# RJ45_Power_Reg.net
KiCad netlist of a schematic drawn in Altium Designer
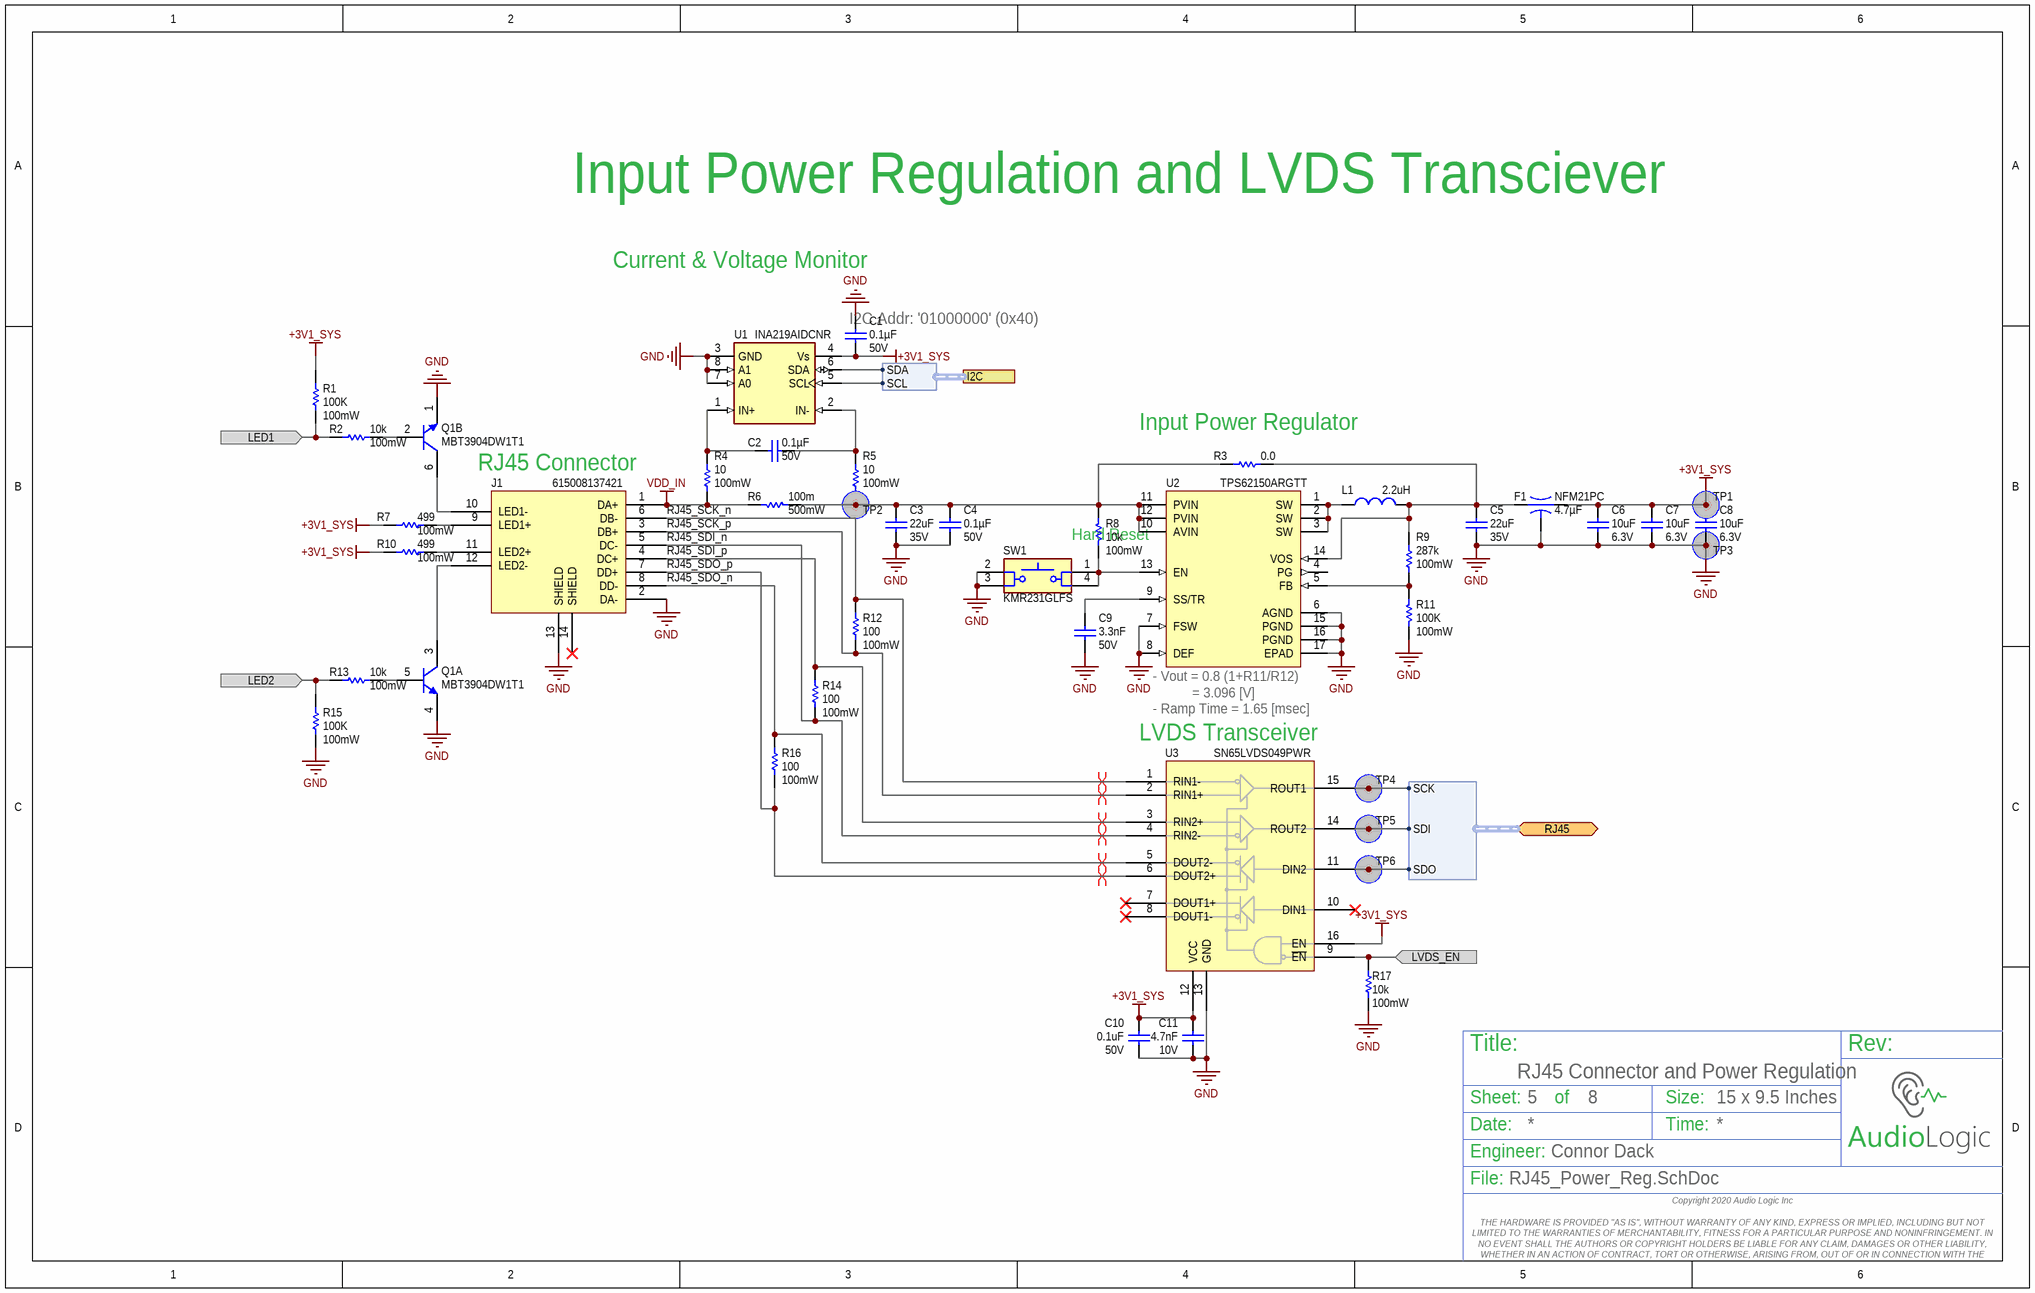
[diagram p0: RJ45_Power_Reg.SchDoc]

(export (version "E")
  (design (tool "Eeschema 10.0.6"))
  (components
    (comp (ref "C1")
      (value "C1005X7R1H104K050BE")
      (footprint "2-0402_L")
      (description "CAP CER 0.1UF 50V X7R 0402")
      (fields
        (field (name "MANUFACTURER") "TDK Corporation")
        (field (name "TOLERANCE") "±10%")
        (field (name "VOLTAGE - RATED") "50V")
        (field (name "CAPACITANCE") "0.1µF")
      )
      (libsource (lib "Schematic_Components") (part "C1005X7R1H104K050BE"))
    )
    (comp (ref "C2")
      (value "C1005X7R1H104K050BE")
      (footprint "2-0402_L")
      (description "CAP CER 0.1UF 50V X7R 0402")
      (fields
        (field (name "MANUFACTURER") "TDK Corporation")
        (field (name "TOLERANCE") "±10%")
        (field (name "VOLTAGE - RATED") "50V")
        (field (name "CAPACITANCE") "0.1µF")
      )
      (libsource (lib "Schematic_Components") (part "C1005X7R1H104K050BE"))
    )
    (comp (ref "C3")
      (value "C3216X5R1V226M160AC")
      (footprint "C1206")
      (description "CAP CER 22UF 35V X5R 1206")
      (fields
        (field (name "MANUFACTURER") "TDK")
        (field (name "TOLERANCE") "20%")
        (field (name "VOLTAGE RATING") "35V")
        (field (name "CAPACITANCE") "22uF")
      )
      (libsource (lib "Schematic_Components") (part "C3216X5R1V226M160AC"))
    )
    (comp (ref "C4")
      (value "C1005X7R1H104K050BE")
      (footprint "2-0402_L")
      (description "CAP CER 0.1UF 50V X7R 0402")
      (fields
        (field (name "MANUFACTURER") "TDK Corporation")
        (field (name "TOLERANCE") "±10%")
        (field (name "VOLTAGE - RATED") "50V")
        (field (name "CAPACITANCE") "0.1µF")
      )
      (libsource (lib "Schematic_Components") (part "C1005X7R1H104K050BE"))
    )
    (comp (ref "C5")
      (value "C3216X5R1V226M160AC")
      (footprint "C1206")
      (description "CAP CER 22UF 35V X5R 1206")
      (fields
        (field (name "MANUFACTURER") "TDK")
        (field (name "TOLERANCE") "20%")
        (field (name "VOLTAGE") "35V")
        (field (name "CAPACITANCE") "22uF")
      )
      (libsource (lib "Schematic_Components") (part "C3216X5R1V226M160AC"))
    )
    (comp (ref "C6")
      (value "JMK107ABJ106MAHT")
      (footprint "3-0603_L")
      (description "CAP CER 10UF 6.3V X5R 0603")
      (fields
        (field (name "MANUFACTURER") "Taiyo Yuden")
        (field (name "TOLERANCE") "20%")
        (field (name "VOLTAGE RATING (DC)") "6.3V")
        (field (name "CAPACITANCE") "10uF")
      )
      (libsource (lib "Schematic_Components") (part "JMK107ABJ106MAHT"))
    )
    (comp (ref "C7")
      (value "JMK107ABJ106MAHT")
      (footprint "3-0603_L")
      (description "CAP CER 10UF 6.3V X5R 0603")
      (fields
        (field (name "MANUFACTURER") "Taiyo Yuden")
        (field (name "TOLERANCE") "20%")
        (field (name "VOLTAGE RATING (DC)") "6.3V")
        (field (name "CAPACITANCE") "10uF")
      )
      (libsource (lib "Schematic_Components") (part "JMK107ABJ106MAHT"))
    )
    (comp (ref "C8")
      (value "JMK107ABJ106MAHT")
      (footprint "3-0603_L")
      (description "CAP CER 10UF 6.3V X5R 0603")
      (fields
        (field (name "MANUFACTURER") "Taiyo Yuden")
        (field (name "TOLERANCE") "20%")
        (field (name "VOLTAGE RATING (DC)") "6.3V")
        (field (name "CAPACITANCE") "10uF")
      )
      (libsource (lib "Schematic_Components") (part "JMK107ABJ106MAHT"))
    )
    (comp (ref "C9")
      (value "04025C332KAT2A")
      (footprint "CAPC1005X56X25NL10T15")
      (description "CAP CER 3300PF 50V X7R 0402")
      (fields
        (field (name "CAPACITANCE") "3.3nF")
        (field (name "MANUFACTURER") "AVX Interconnect / Elco")
        (field (name "TOLERANCE") "10%")
        (field (name "VOLTAGE RATING") "50V")
      )
      (libsource (lib "Altium Content Vault") (part "CAP"))
    )
    (comp (ref "C10")
      (value "UMK105B7104KVHF")
      (footprint "2-0402_L")
      (description "CAP CER 0.1uF 50V X7R +/-10% 0402 AEC-Q200")
      (fields
        (field (name "MANUFACTURER") "Taiyo Yuden")
        (field (name "TOLERANCE") "10%")
        (field (name "CAPACITANCE") "0.1uF")
        (field (name "VOLTAGE RATING") "50V")
      )
      (libsource (lib "Schematic_Components") (part "UMK105B7104KVHF"))
    )
    (comp (ref "C11")
      (value "C0603C472K8RACTU")
      (footprint "3-0603_L")
      (description "CAP CER 4700PF 10V X7R 0603")
      (fields
        (field (name "MANUFACTURER") "KEMET")
        (field (name "TOLERANCE") "10%")
        (field (name "VOLTAGE RATING (DC)") "10V")
        (field (name "CAPACITANCE") "4.7nF")
      )
      (libsource (lib "Schematic_Components_CD") (part "C0603C472K8RACTU"))
    )
    (comp (ref "F1")
      (value "NFM21PC")
      (footprint "NFM21PC")
      (description "CAP FEEDTHRU 4.7UF 20% 10V 0805")
      (fields
        (field (name "MANUFACTURER") "Murata Electronics North America")
        (field (name "TOLERANCE") "±20%")
        (field (name "CAPACITANCE") "4.7µF")
      )
      (libsource (lib "Schematic_Components") (part "NFM21PC475B1A3D"))
    )
    (comp (ref "J1")
      (value "CONN MOD JACK 8P8C R/A SHIELDED")
      (footprint "RJ45")
      (description "Jack Modular Connector 8p8c (RJ45, Ethernet) 90° Angle (Right) Shielded, EMI Finger Cat5")
      (fields
        (field (name "MANUFACTURER") "Wurth Electronics")
        (field (name "MANUFACTURER PART NUMBER") "615008137421")
      )
      (libsource (lib "Schematic_Components_CD") (part "615008137421"))
    )
    (comp (ref "L1")
      (value "2.2uH Ind")
      (footprint "XFL4020")
      (description "Fixed Inductors XFL4020 AEC-Q200 2.2 uH 20 % 8 A")
      (fields
        (field (name "MANUFACTURER") "Coilcraft")
        (field (name "MANUFACTURER PART NUMBER") "XFL4020-222MEB")
        (field (name "INDUCTANCE") "2.2uH")
      )
      (libsource (lib "Schematic_Components_CD") (part "XFL4020-222MEB"))
    )
    (comp (ref "Q1")
      (value "MBT3904DW1T1")
      (footprint "ADI-KS-6_SC70_L")
      (description "TRANS DUAL GP 200MA 40V SC88")
      (fields
        (field (name "MANUFACTURER") "ON Semiconductor")
        (field (name "MANUFACTURER PART NUMBER") "MBT3904DW1T1G")
        (field (name "SYMNAME") "MBT3904DW1T1")
      )
      (libsource (lib "Schematic_Components") (part "MBT3904DW1T1"))
    )
    (comp (ref "R1")
      (value "ERJ-2RKF1003X")
      (footprint "2-0402_R_L")
      (description "RES 100K OHM 1/10W 1% 0402 SMD")
      (fields
        (field (name "MANUFACTURER") "Panasonic - ECG")
        (field (name "POWER (WATTS)") "100mW")
        (field (name "TOLERANCE") "±1%")
        (field (name "RESISTANCE (OHMS)") "100K")
      )
      (libsource (lib "Schematic_Components") (part "ERJ-2RKF1003X"))
    )
    (comp (ref "R2")
      (value "ERJ-2RKF1002X")
      (footprint "2-0402_R_L")
      (description "RES 10K OHM 1/10W 1% 0402 SMD")
      (fields
        (field (name "MANUFACTURER") "Panasonic Electronic Components")
        (field (name "TOLERANCE") "±1%")
        (field (name "POWER (WATTS)") "100mW")
        (field (name "RESISTANCE (OHMS)") "10k")
      )
      (libsource (lib "Schematic_Components") (part "ERJ-2RKF1002X"))
    )
    (comp (ref "R3")
      (value "ERJ-6GEY0R00V")
      (footprint "6-0805_R_L")
      (description "RES 0.0 OHM 1/8W 0805 SMD")
      (fields
        (field (name "MANUFACTURER") "Panasonic - ECG")
        (field (name "TOLERANCE") "Jumper")
        (field (name "RESISTANCE (OHMS)") "0.0")
      )
      (libsource (lib "Schematic_Components") (part "ERJ-6GEY0R00V"))
    )
    (comp (ref "R4")
      (value "ERJ-2RKF10R0X")
      (footprint "2-0402_R_L")
      (description "RES 10 OHM 1/10W 1% 0402 SMD")
      (fields
        (field (name "MANUFACTURER") "Panasonic Electronic Components")
        (field (name "TOLERANCE") "±1%")
        (field (name "POWER (WATTS)") "100mW")
        (field (name "RESISTANCE (OHMS)") "10")
      )
      (libsource (lib "Schematic_Components") (part "ERJ-2RKF10R0X"))
    )
    (comp (ref "R5")
      (value "ERJ-2RKF10R0X")
      (footprint "2-0402_R_L")
      (description "RES 10 OHM 1/10W 1% 0402 SMD")
      (fields
        (field (name "MANUFACTURER") "Panasonic Electronic Components")
        (field (name "TOLERANCE") "±1%")
        (field (name "POWER (WATTS)") "100mW")
        (field (name "RESISTANCE (OHMS)") "10")
      )
      (libsource (lib "Schematic_Components") (part "ERJ-2RKF10R0X"))
    )
    (comp (ref "R6")
      (value "ERJ-6DSFR10V")
      (footprint "6-0805_R_L")
      (description "RES SMD 0.1 OHM 1% 1/2W 0805")
      (fields
        (field (name "MANUFACTURER") "Panasonic")
        (field (name "TOLERANCE") "1%")
        (field (name "MAX POWER DISSIPATION") "500mW")
        (field (name "RESISTANCE") "100m")
      )
      (libsource (lib "Schematic_Components") (part "ERJ-6DSFR10V"))
    )
    (comp (ref "R7")
      (value "ERJ-2RKF4990X")
      (footprint "2-0402_R_L")
      (description "RES 499 OHM 1/10W 1% 0402 SMD")
      (fields
        (field (name "MANUFACTURER") "Panasonic Electronic Components")
        (field (name "TOLERANCE") "±1%")
        (field (name "POWER (WATTS)") "100mW")
        (field (name "RESISTANCE (OHMS)") "499")
      )
      (libsource (lib "Schematic_Components") (part "ERJ-2RKF4990X"))
    )
    (comp (ref "R8")
      (value "ERJ-2RKF1002X")
      (footprint "2-0402_R_L")
      (description "RES 10K OHM 1/10W 1% 0402 SMD")
      (fields
        (field (name "MANUFACTURER") "Panasonic Electronic Components")
        (field (name "TOLERANCE") "±1%")
        (field (name "POWER (WATTS)") "100mW")
        (field (name "RESISTANCE (OHMS)") "10k")
      )
      (libsource (lib "Schematic_Components") (part "ERJ-2RKF1002X"))
    )
    (comp (ref "R9")
      (value "ERJ-2RKF2873X")
      (footprint "RESC1005X40X25NL05T05")
      (description "RES SMD 287K OHM 1% 1/10W 0402")
      (fields
        (field (name "MANUFACTURER") "Panasonic")
        (field (name "RESISTANCE") "287k")
        (field (name "POWER RATING") "100mW")
        (field (name "TOLERANCE") "1%")
      )
      (libsource (lib "Altium Content Vault") (part "RES"))
    )
    (comp (ref "R10")
      (value "ERJ-2RKF4990X")
      (footprint "2-0402_R_L")
      (description "RES 499 OHM 1/10W 1% 0402 SMD")
      (fields
        (field (name "MANUFACTURER") "Panasonic Electronic Components")
        (field (name "TOLERANCE") "±1%")
        (field (name "POWER (WATTS)") "100mW")
        (field (name "RESISTANCE (OHMS)") "499")
      )
      (libsource (lib "Schematic_Components") (part "ERJ-2RKF4990X"))
    )
    (comp (ref "R11")
      (value "ERJ-2RKF1003X")
      (footprint "2-0402_R_L")
      (description "RES 100K OHM 1/10W 1% 0402 SMD")
      (fields
        (field (name "MANUFACTURER") "Panasonic - ECG")
        (field (name "POWER (WATTS)") "100mW")
        (field (name "TOLERANCE") "±1%")
        (field (name "RESISTANCE (OHMS)") "100K")
      )
      (libsource (lib "Schematic_Components") (part "ERJ-2RKF1003X"))
    )
    (comp (ref "R12")
      (value "ERJ-2RKF1000X")
      (footprint "2-0402_R_L")
      (description "RES 100 OHM 1/10W 1% 0402 SMD")
      (fields
        (field (name "MANUFACTURER") "Panasonic Electronic Components")
        (field (name "POWER (WATTS)") "100mW")
        (field (name "TOLERANCE") "±1%")
        (field (name "RESISTANCE (OHMS)") "100")
      )
      (libsource (lib "Schematic_Components") (part "ERJ-2RKF1000X"))
    )
    (comp (ref "R13")
      (value "ERJ-2RKF1002X")
      (footprint "2-0402_R_L")
      (description "RES 10K OHM 1/10W 1% 0402 SMD")
      (fields
        (field (name "MANUFACTURER") "Panasonic Electronic Components")
        (field (name "TOLERANCE") "±1%")
        (field (name "POWER (WATTS)") "100mW")
        (field (name "RESISTANCE (OHMS)") "10k")
      )
      (libsource (lib "Schematic_Components") (part "ERJ-2RKF1002X"))
    )
    (comp (ref "R14")
      (value "ERJ-2RKF1000X")
      (footprint "2-0402_R_L")
      (description "RES 100 OHM 1/10W 1% 0402 SMD")
      (fields
        (field (name "MANUFACTURER") "Panasonic Electronic Components")
        (field (name "POWER (WATTS)") "100mW")
        (field (name "TOLERANCE") "±1%")
        (field (name "RESISTANCE (OHMS)") "100")
      )
      (libsource (lib "Schematic_Components") (part "ERJ-2RKF1000X"))
    )
    (comp (ref "R15")
      (value "ERJ-2RKF1003X")
      (footprint "2-0402_R_L")
      (description "RES 100K OHM 1/10W 1% 0402 SMD")
      (fields
        (field (name "MANUFACTURER") "Panasonic - ECG")
        (field (name "POWER (WATTS)") "100mW")
        (field (name "TOLERANCE") "±1%")
        (field (name "RESISTANCE (OHMS)") "100K")
      )
      (libsource (lib "Schematic_Components") (part "ERJ-2RKF1003X"))
    )
    (comp (ref "R16")
      (value "ERJ-2RKF1000X")
      (footprint "2-0402_R_L")
      (description "RES 100 OHM 1/10W 1% 0402 SMD")
      (fields
        (field (name "MANUFACTURER") "Panasonic Electronic Components")
        (field (name "POWER (WATTS)") "100mW")
        (field (name "TOLERANCE") "±1%")
        (field (name "RESISTANCE (OHMS)") "100")
      )
      (libsource (lib "Schematic_Components") (part "ERJ-2RKF1000X"))
    )
    (comp (ref "R17")
      (value "ERJ-2RKF1002X")
      (footprint "2-0402_R_L")
      (description "RES 10K OHM 1/10W 1% 0402 SMD")
      (fields
        (field (name "MANUFACTURER") "Panasonic Electronic Components")
        (field (name "TOLERANCE") "±1%")
        (field (name "POWER (WATTS)") "100mW")
        (field (name "RESISTANCE (OHMS)") "10k")
      )
      (libsource (lib "Schematic_Components") (part "ERJ-2RKF1002X"))
    )
    (comp (ref "SW1")
      (value "SPST-NO")
      (footprint "CKCP-KMR231GLFS")
      (description "SWITCH TACTILE SPST-NO 0.05A 32V")
      (fields (field (name "MANUFACTURER") "ITT C&K") (field (name "MANUFACTURER PART NUMBER") "KMR231GLFS"))
      (libsource (lib "Schematic_Components") (part "SW-SPST-NO_KMR231GLFS"))
    )
    (comp (ref "TP1")
      (value "Testpoint")
      (footprint "Testpoint_SMT")
      (description "Testpoint, 1-Pin, SMT")
      (libsource (lib "Schematic_Components") (part "Testpoint_SMT"))
    )
    (comp (ref "TP2")
      (value "Testpoint")
      (footprint "Testpoint_SMT2")
      (description "Testpoint, 1-Pin, SMT")
      (libsource (lib "Schematic_Components") (part "Testpoint_SMT"))
    )
    (comp (ref "TP3")
      (value "Testpoint")
      (footprint "Testpoint_SMT2")
      (description "Testpoint, 1-Pin, SMT")
      (libsource (lib "Schematic_Components") (part "Testpoint_SMT"))
    )
    (comp (ref "TP4")
      (value "Testpoint")
      (footprint "Testpoint_SMT")
      (description "Testpoint, 1-Pin, SMT")
      (libsource (lib "Schematic_Components") (part "Testpoint_SMT"))
    )
    (comp (ref "TP5")
      (value "Testpoint")
      (footprint "Testpoint_SMT")
      (description "Testpoint, 1-Pin, SMT")
      (libsource (lib "Schematic_Components") (part "Testpoint_SMT"))
    )
    (comp (ref "TP6")
      (value "Testpoint")
      (footprint "Testpoint_SMT")
      (description "Testpoint, 1-Pin, SMT")
      (libsource (lib "Schematic_Components") (part "Testpoint_SMT"))
    )
    (comp (ref "U1")
      (value "INA219AIDCNR")
      (footprint "SOT23-8")
      (description "IC CURRENT MONITOR 1% SOT23-8")
      (fields
        (field (name "MANUFACTURER") "Texas Instruments")
        (field (name "MANUFACTURER PART NUMBER") "INA219AIDCNR")
      )
      (libsource (lib "Schematic_Components") (part "INA219AIDCNR"))
    )
    (comp (ref "U2")
      (value "TPS62150ARGTT")
      (footprint "QFN50P300X300X100_HS-17N")
      (fields (field (name "MANUFACTURER") "Texas Instruments"))
      (libsource (lib "Schematic_Components_CD") (part "TPS62150ARGTT"))
    )
    (comp (ref "U3")
      (value "SN65LVDS049PWR")
      (footprint "TSOP65P640X120-16N")
      (description "IC LVDS DUAL DIF DVR/RCV 16TSSOP")
      (fields (field (name "MANUFACTURER") "Texas Instruments"))
      (libsource (lib "Schematic_Components_CD") (part "SN65LVDS049PWR"))
    )
  )
  (nets
    (net (code "3") (name "+3V1_SYS") (class "Default")
      (node (ref "C1") (pin "1") (pinfunction "1_1") (pintype "passive"))
      (node (ref "C10") (pin "2") (pinfunction "2_2") (pintype "passive"))
      (node (ref "C11") (pin "2") (pinfunction "2_2") (pintype "passive"))
      (node (ref "C6") (pin "2") (pinfunction "2_2") (pintype "passive"))
      (node (ref "C7") (pin "2") (pinfunction "2_2") (pintype "passive"))
      (node (ref "C8") (pin "2") (pinfunction "2_2") (pintype "passive"))
      (node (ref "F1") (pin "3") (pinfunction "OUT_3") (pintype "passive"))
      (node (ref "R1") (pin "2") (pinfunction "2_2") (pintype "passive"))
      (node (ref "R10") (pin "2") (pinfunction "2_2") (pintype "passive"))
      (node (ref "R7") (pin "2") (pinfunction "2_2") (pintype "passive"))
      (node (ref "TP1") (pin "1") (pinfunction "1_1") (pintype "passive"))
      (node (ref "U1") (pin "4") (pinfunction "Vs_4") (pintype "power_in"))
      (node (ref "U3") (pin "12") (pinfunction "VCC_12") (pintype "power_in"))
      (node (ref "U3") (pin "16") (pinfunction "EN_16") (pintype "passive"))
    )
    (net (code "4") (name "/LED1") (class "Default")
      (node (ref "R1") (pin "1") (pinfunction "1_1") (pintype "passive"))
      (node (ref "R2") (pin "2") (pinfunction "2_2") (pintype "passive"))
    )
    (net (code "5") (name "/LED2") (class "Default")
      (node (ref "R13") (pin "2") (pinfunction "2_2") (pintype "passive"))
      (node (ref "R15") (pin "2") (pinfunction "2_2") (pintype "passive"))
    )
    (net (code "6") (name "/LVDS_EN") (class "Default")
      (node (ref "R17") (pin "2") (pinfunction "2_2") (pintype "passive"))
      (node (ref "U3") (pin "9") (pinfunction "~{EN}_9") (pintype "passive"))
    )
    (net (code "7") (name "/RJ45_SCK_n") (class "Default")
      (node (ref "J1") (pin "6") (pinfunction "DB-_6") (pintype "passive"))
      (node (ref "R12") (pin "2") (pinfunction "2_2") (pintype "passive"))
      (node (ref "U3") (pin "1") (pinfunction "RIN1-_1") (pintype "passive"))
    )
    (net (code "8") (name "/RJ45_SCK_p") (class "Default")
      (node (ref "J1") (pin "3") (pinfunction "DB+_3") (pintype "passive"))
      (node (ref "R12") (pin "1") (pinfunction "1_1") (pintype "passive"))
      (node (ref "U3") (pin "2") (pinfunction "RIN1+_2") (pintype "passive"))
    )
    (net (code "9") (name "/RJ45_SDI_n") (class "Default")
      (node (ref "J1") (pin "5") (pinfunction "DC-_5") (pintype "passive"))
      (node (ref "R14") (pin "1") (pinfunction "1_1") (pintype "passive"))
      (node (ref "U3") (pin "4") (pinfunction "RIN2-_4") (pintype "passive"))
    )
    (net (code "10") (name "/RJ45_SDI_p") (class "Default")
      (node (ref "J1") (pin "4") (pinfunction "DC+_4") (pintype "passive"))
      (node (ref "R14") (pin "2") (pinfunction "2_2") (pintype "passive"))
      (node (ref "U3") (pin "3") (pinfunction "RIN2+_3") (pintype "passive"))
    )
    (net (code "11") (name "/RJ45_SDO_n") (class "Default")
      (node (ref "J1") (pin "8") (pinfunction "DD-_8") (pintype "passive"))
      (node (ref "R16") (pin "2") (pinfunction "2_2") (pintype "passive"))
      (node (ref "U3") (pin "5") (pinfunction "DOUT2-_5") (pintype "passive"))
    )
    (net (code "12") (name "/RJ45_SDO_p") (class "Default")
      (node (ref "J1") (pin "7") (pinfunction "DD+_7") (pintype "passive"))
      (node (ref "R16") (pin "1") (pinfunction "1_1") (pintype "passive"))
      (node (ref "U3") (pin "6") (pinfunction "DOUT2+_6") (pintype "passive"))
    )
    (net (code "13") (name "/SCK") (class "Default")
      (node (ref "TP4") (pin "1") (pinfunction "1_1") (pintype "passive"))
      (node (ref "U3") (pin "15") (pinfunction "ROUT1_15") (pintype "passive"))
    )
    (net (code "14") (name "/SCL") (class "Default")
      (node (ref "U1") (pin "5") (pinfunction "SCL_5") (pintype "input"))
    )
    (net (code "15") (name "/SDA") (class "Default")
      (node (ref "U1") (pin "6") (pinfunction "SDA_6") (pintype "bidirectional"))
    )
    (net (code "16") (name "/SDI") (class "Default")
      (node (ref "TP5") (pin "1") (pinfunction "1_1") (pintype "passive"))
      (node (ref "U3") (pin "14") (pinfunction "ROUT2_14") (pintype "passive"))
    )
    (net (code "17") (name "/SDO") (class "Default")
      (node (ref "TP6") (pin "1") (pinfunction "1_1") (pintype "passive"))
      (node (ref "U3") (pin "11") (pinfunction "DIN2_11") (pintype "passive"))
    )
    (net (code "20") (name "GND") (class "Default")
      (node (ref "C1") (pin "2") (pinfunction "2_2") (pintype "passive"))
      (node (ref "C10") (pin "1") (pinfunction "1_1") (pintype "passive"))
      (node (ref "C11") (pin "1") (pinfunction "1_1") (pintype "passive"))
      (node (ref "C3") (pin "1") (pinfunction "1_1") (pintype "passive"))
      (node (ref "C4") (pin "1") (pinfunction "1_1") (pintype "passive"))
      (node (ref "C5") (pin "1") (pinfunction "1_1") (pintype "passive"))
      (node (ref "C6") (pin "1") (pinfunction "1_1") (pintype "passive"))
      (node (ref "C7") (pin "1") (pinfunction "1_1") (pintype "passive"))
      (node (ref "C8") (pin "1") (pinfunction "1_1") (pintype "passive"))
      (node (ref "C9") (pin "1") (pinfunction "1_1") (pintype "passive"))
      (node (ref "F1") (pin "2") (pinfunction "GND_2") (pintype "passive"))
      (node (ref "J1") (pin "13") (pinfunction "SHIELD_13") (pintype "passive"))
      (node (ref "J1") (pin "2") (pinfunction "DA-_2") (pintype "passive"))
      (node (ref "Q1") (pin "1") (pinfunction "E_1") (pintype "passive"))
      (node (ref "Q1") (pin "4") (pinfunction "E_4") (pintype "passive"))
      (node (ref "R11") (pin "1") (pinfunction "1_1") (pintype "passive"))
      (node (ref "R15") (pin "1") (pinfunction "1_1") (pintype "passive"))
      (node (ref "R17") (pin "1") (pinfunction "1_1") (pintype "passive"))
      (node (ref "SW1") (pin "2") (pinfunction "2_2") (pintype "passive"))
      (node (ref "SW1") (pin "3") (pinfunction "3_3") (pintype "passive"))
      (node (ref "TP3") (pin "1") (pinfunction "1_1") (pintype "passive"))
      (node (ref "U1") (pin "3") (pinfunction "GND_3") (pintype "power_in"))
      (node (ref "U1") (pin "7") (pinfunction "A0_7") (pintype "input"))
      (node (ref "U1") (pin "8") (pinfunction "A1_8") (pintype "input"))
      (node (ref "U2") (pin "15") (pinfunction "PGND_15") (pintype "power_in"))
      (node (ref "U2") (pin "16") (pinfunction "PGND_16") (pintype "power_in"))
      (node (ref "U2") (pin "17") (pinfunction "EPAD_17") (pintype "power_in"))
      (node (ref "U2") (pin "6") (pinfunction "AGND_6") (pintype "power_in"))
      (node (ref "U2") (pin "7") (pinfunction "FSW_7") (pintype "input"))
      (node (ref "U2") (pin "8") (pinfunction "DEF_8") (pintype "input"))
      (node (ref "U3") (pin "13") (pinfunction "GND_13") (pintype "power_in"))
    )
    (net (code "21") (name "Net-(F1-IN)") (class "Default")
      (node (ref "C5") (pin "2") (pinfunction "2_2") (pintype "passive"))
      (node (ref "F1") (pin "1") (pinfunction "IN_1") (pintype "passive"))
      (node (ref "L1") (pin "2") (pinfunction "2_2") (pintype "passive"))
      (node (ref "R3") (pin "2") (pinfunction "2_2") (pintype "passive"))
      (node (ref "R9") (pin "2") (pinfunction "2_2") (pintype "passive"))
      (node (ref "U2") (pin "14") (pinfunction "VOS_14") (pintype "input"))
    )
    (net (code "22") (name "Net-(J1-LED1+)") (class "Default")
      (node (ref "J1") (pin "9") (pinfunction "LED1+_9") (pintype "passive"))
      (node (ref "R7") (pin "1") (pinfunction "1_1") (pintype "passive"))
    )
    (net (code "23") (name "Net-(J1-LED1-)") (class "Default")
      (node (ref "J1") (pin "10") (pinfunction "LED1-_10") (pintype "passive"))
      (node (ref "Q1") (pin "6") (pinfunction "C_6") (pintype "passive"))
    )
    (net (code "24") (name "Net-(J1-LED2+)") (class "Default")
      (node (ref "J1") (pin "11") (pinfunction "LED2+_11") (pintype "passive"))
      (node (ref "R10") (pin "1") (pinfunction "1_1") (pintype "passive"))
    )
    (net (code "25") (name "Net-(J1-LED2-)") (class "Default")
      (node (ref "J1") (pin "12") (pinfunction "LED2-_12") (pintype "passive"))
      (node (ref "Q1") (pin "3") (pinfunction "C_3") (pintype "passive"))
    )
    (net (code "26") (name "Net-(L1-Pad1)") (class "Default")
      (node (ref "L1") (pin "1") (pinfunction "1_1") (pintype "passive"))
      (node (ref "U2") (pin "1") (pinfunction "SW_1") (pintype "power_in"))
      (node (ref "U2") (pin "2") (pinfunction "SW_2") (pintype "power_in"))
      (node (ref "U2") (pin "3") (pinfunction "SW_3") (pintype "power_in"))
    )
    (net (code "27") (name "Net-(Q1A-B)") (class "Default")
      (node (ref "Q1") (pin "5") (pinfunction "B_5") (pintype "passive"))
      (node (ref "R13") (pin "1") (pinfunction "1_1") (pintype "passive"))
    )
    (net (code "28") (name "Net-(Q1B-B)") (class "Default")
      (node (ref "Q1") (pin "2") (pinfunction "B_2") (pintype "passive"))
      (node (ref "R2") (pin "1") (pinfunction "1_1") (pintype "passive"))
    )
    (net (code "29") (name "Net-(U1-IN+)") (class "Default")
      (node (ref "C2") (pin "1") (pinfunction "1_1") (pintype "passive"))
      (node (ref "R4") (pin "2") (pinfunction "2_2") (pintype "passive"))
      (node (ref "U1") (pin "1") (pinfunction "IN+_1") (pintype "input"))
    )
    (net (code "30") (name "Net-(U1-IN-)") (class "Default")
      (node (ref "C2") (pin "2") (pinfunction "2_2") (pintype "passive"))
      (node (ref "R5") (pin "2") (pinfunction "2_2") (pintype "passive"))
      (node (ref "U1") (pin "2") (pinfunction "IN-_2") (pintype "input"))
    )
    (net (code "31") (name "Net-(U2-AVIN)") (class "Default")
      (node (ref "C3") (pin "2") (pinfunction "2_2") (pintype "passive"))
      (node (ref "C4") (pin "2") (pinfunction "2_2") (pintype "passive"))
      (node (ref "R3") (pin "1") (pinfunction "1_1") (pintype "passive"))
      (node (ref "R5") (pin "1") (pinfunction "1_1") (pintype "passive"))
      (node (ref "R6") (pin "1") (pinfunction "1_1") (pintype "passive"))
      (node (ref "R8") (pin "2") (pinfunction "2_2") (pintype "passive"))
      (node (ref "TP2") (pin "1") (pinfunction "1_1") (pintype "passive"))
      (node (ref "U2") (pin "10") (pinfunction "AVIN_10") (pintype "power_in"))
      (node (ref "U2") (pin "11") (pinfunction "PVIN_11") (pintype "power_in"))
      (node (ref "U2") (pin "12") (pinfunction "PVIN_12") (pintype "power_in"))
    )
    (net (code "32") (name "Net-(U2-EN)") (class "Default")
      (node (ref "R8") (pin "1") (pinfunction "1_1") (pintype "passive"))
      (node (ref "SW1") (pin "1") (pinfunction "1_1") (pintype "passive"))
      (node (ref "SW1") (pin "4") (pinfunction "4_4") (pintype "passive"))
      (node (ref "U2") (pin "13") (pinfunction "EN_13") (pintype "input"))
    )
    (net (code "33") (name "Net-(U2-FB)") (class "Default")
      (node (ref "R11") (pin "2") (pinfunction "2_2") (pintype "passive"))
      (node (ref "R9") (pin "1") (pinfunction "1_1") (pintype "passive"))
      (node (ref "U2") (pin "5") (pinfunction "FB_5") (pintype "input"))
    )
    (net (code "34") (name "Net-(U2-SS{slash}TR)") (class "Default")
      (node (ref "C9") (pin "2") (pinfunction "2_2") (pintype "passive"))
      (node (ref "U2") (pin "9") (pinfunction "SS/TR_9") (pintype "input"))
    )
    (net (code "35") (name "VDD_IN") (class "Default")
      (node (ref "J1") (pin "1") (pinfunction "DA+_1") (pintype "passive"))
      (node (ref "R4") (pin "1") (pinfunction "1_1") (pintype "passive"))
      (node (ref "R6") (pin "2") (pinfunction "2_2") (pintype "passive"))
    )
    (net (code "36") (name "unconnected-(J1-SHIELD-Pad14)") (class "Default")
      (node (ref "J1") (pin "14") (pinfunction "SHIELD_14") (pintype "passive+no_connect"))
    )
    (net (code "37") (name "unconnected-(SW1-GND-Pad5)") (class "Default")
      (node (ref "SW1") (pin "5") (pinfunction "GND_5") (pintype "passive"))
    )
    (net (code "38") (name "unconnected-(U2-PG-Pad4)") (class "Default")
      (node (ref "U2") (pin "4") (pinfunction "PG_4") (pintype "output"))
    )
    (net (code "39") (name "unconnected-(U3-DIN1-Pad10)") (class "Default")
      (node (ref "U3") (pin "10") (pinfunction "DIN1_10") (pintype "passive+no_connect"))
    )
    (net (code "40") (name "unconnected-(U3-DOUT1+-Pad7)") (class "Default")
      (node (ref "U3") (pin "7") (pinfunction "DOUT1+_7") (pintype "passive+no_connect"))
    )
    (net (code "41") (name "unconnected-(U3-DOUT1--Pad8)") (class "Default")
      (node (ref "U3") (pin "8") (pinfunction "DOUT1-_8") (pintype "passive+no_connect"))
    )
  )
)
